# 1-Schematic_hackcard.net
KiCad netlist of a schematic drawn in EasyEDA
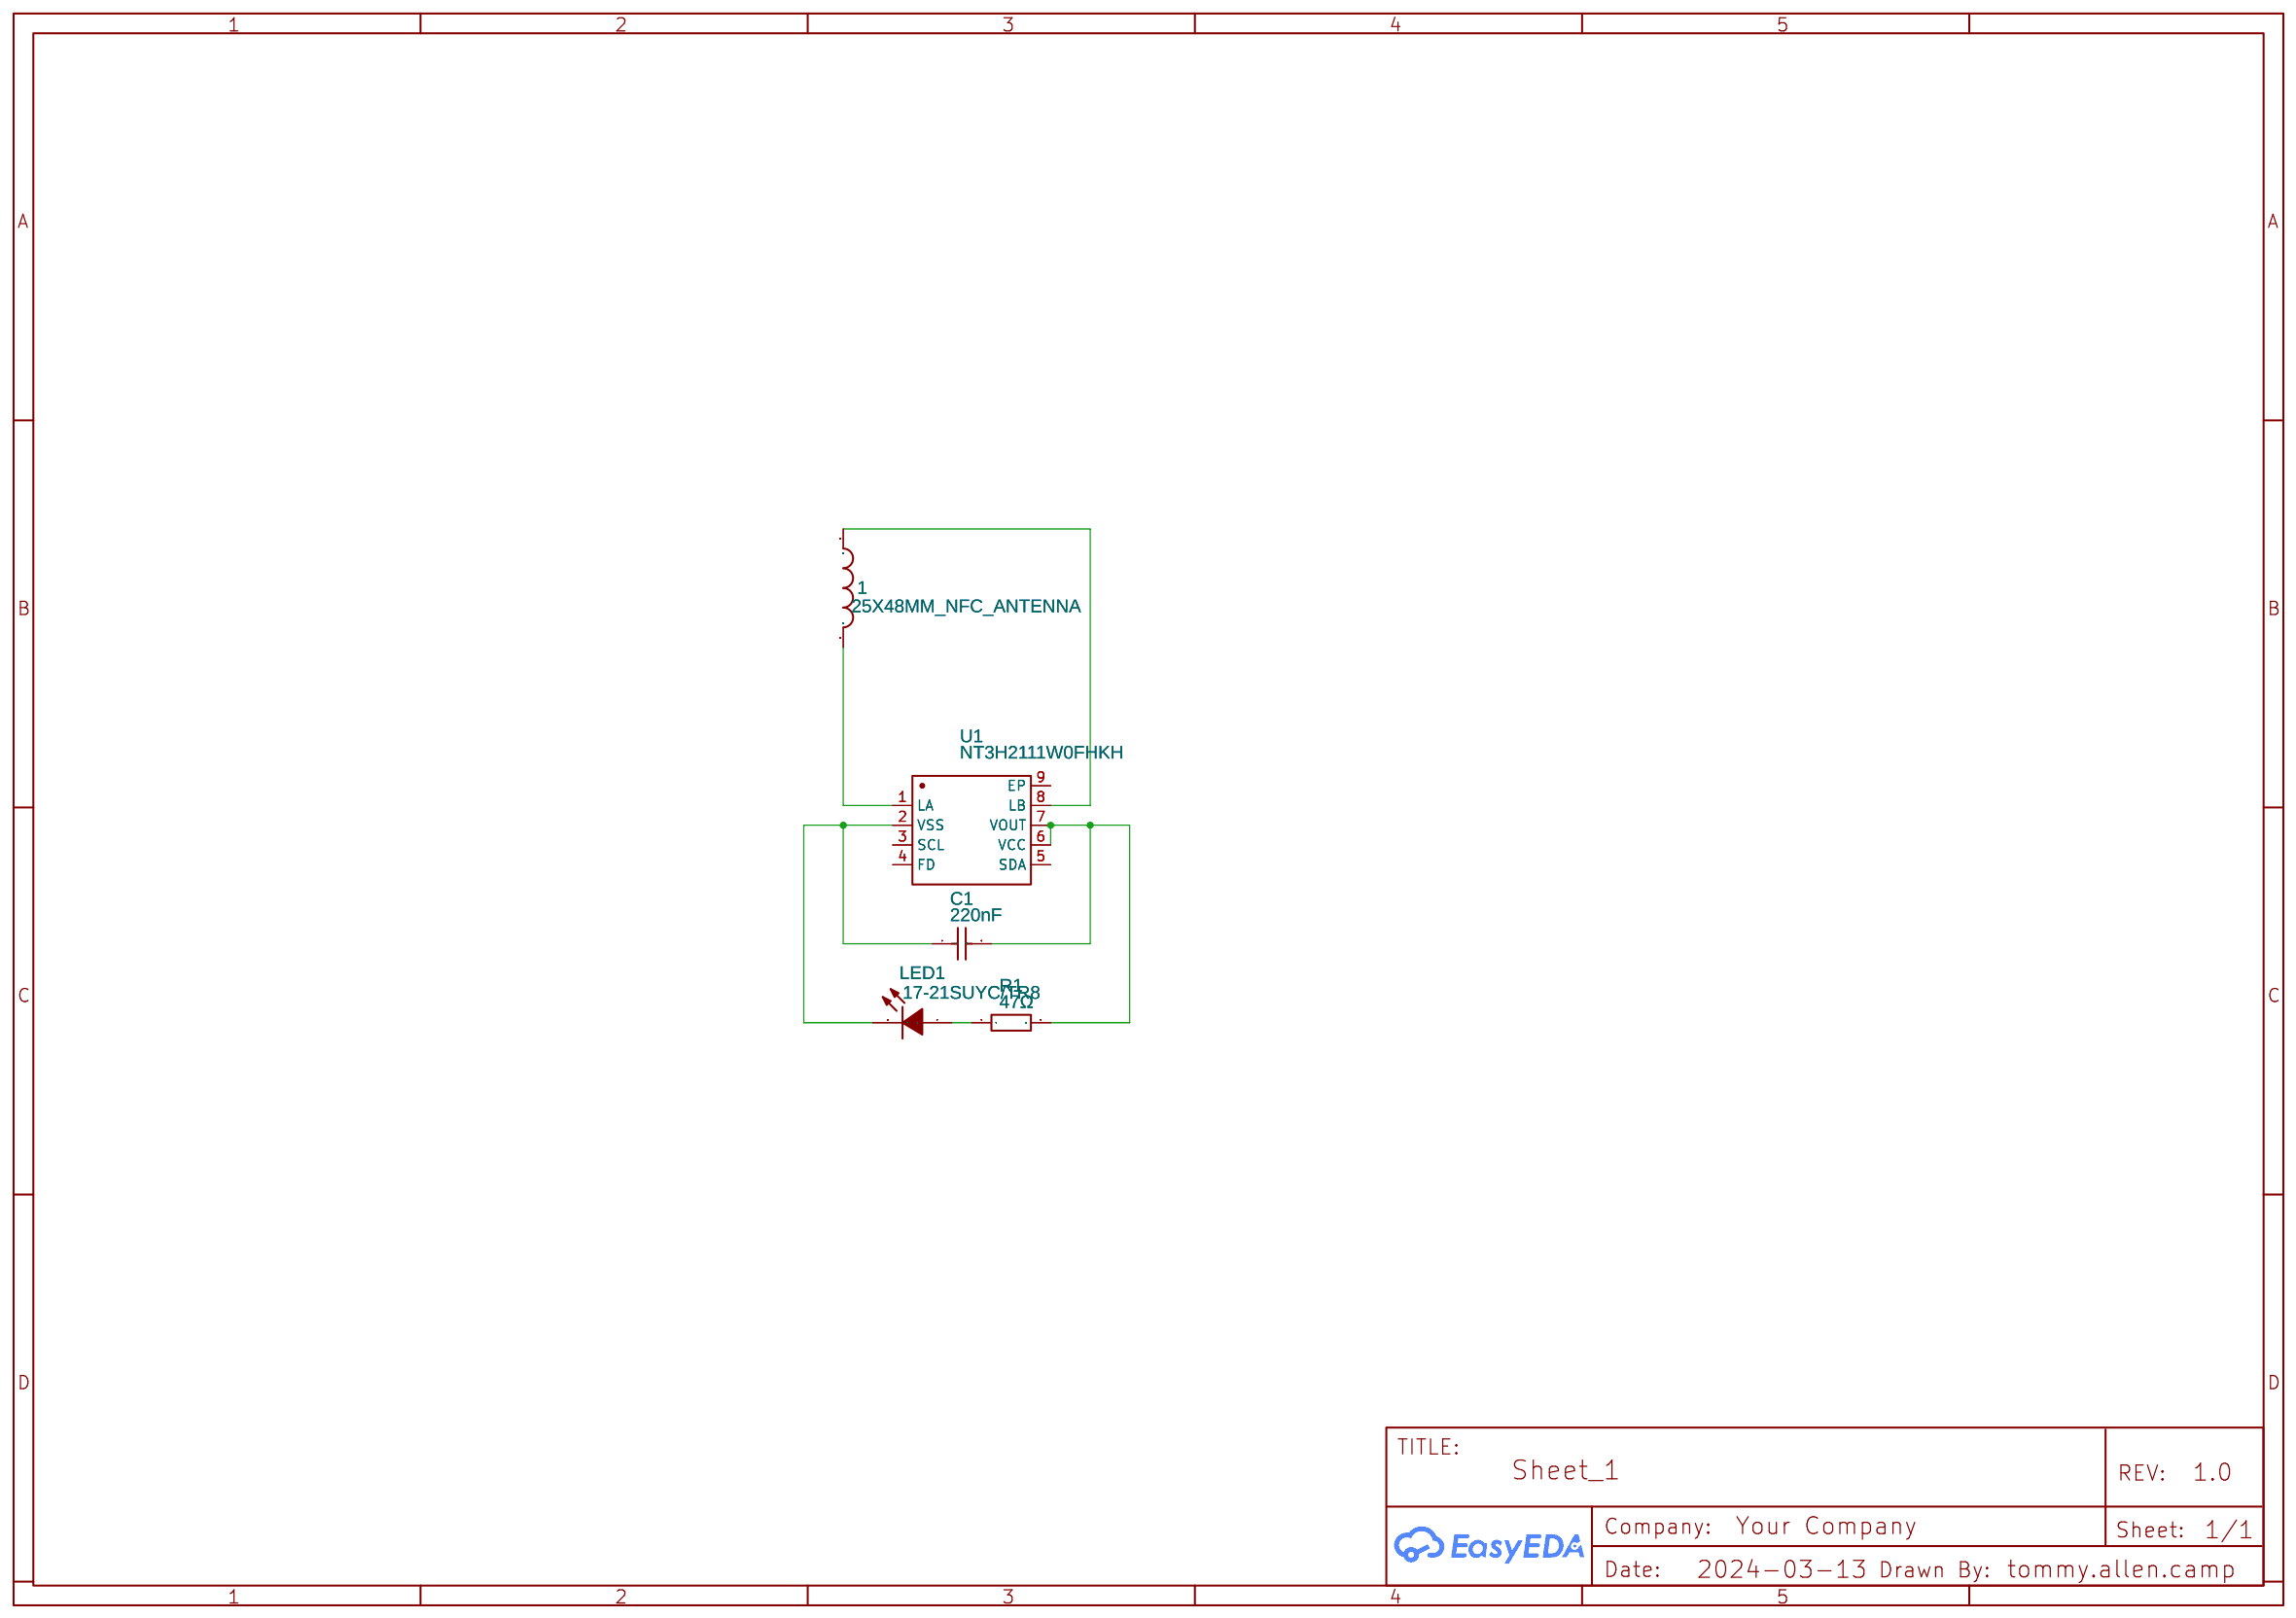
[diagram p0: schematic sheet]

(export (version "E")
  (design (tool "Eeschema 10.0.6"))
  (components
    (comp (ref "1") (value "25X48MM_NFC_ANTENNA") (libsource (lib "") (part "25X48MM_NFC_ANTENNA")))
    (comp (ref "C1")
      (value "220nF")
      (fields
        (field (name "Manufacturer Part") "CL10B224KA8NNNC")
        (field (name "Manufacturer") "SAMSUNG(三星)")
      )
      (libsource (lib "") (part "CL10B224KA8NNNC"))
    )
    (comp (ref "LED1")
      (value "17-21SUYC/TR8")
      (fields (field (name "Manufacturer Part") "KT-0805黄灯") (field (name "Manufacturer") "KENTO"))
      (libsource (lib "") (part "17-21SUYC/TR8"))
    )
    (comp (ref "R1")
      (value "47Ω")
      (fields
        (field (name "Manufacturer Part") "0603WAF470JT5E")
        (field (name "Manufacturer") "UNI-ROYAL(厚声)")
      )
      (libsource (lib "") (part "0603WAF470JT5E"))
    )
    (comp (ref "U1")
      (value "NT3H2111W0FHKH")
      (fields (field (name "Manufacturer") "NXP(恩智浦)"))
      (libsource (lib "") (part "NT3H2111W0FHKH"))
    )
  )
  (nets
    (net (code "1") (name "Net-(LED1-+)") (class "Default")
      (node (ref "LED1") (pin "1") (pinfunction "+_1") (pintype "unspecified"))
      (node (ref "R1") (pin "1") (pinfunction "1_1") (pintype "input"))
    )
    (net (code "2") (name "Net-(LED1--)") (class "Default")
      (node (ref "C1") (pin "1") (pinfunction "1_1") (pintype "input"))
      (node (ref "LED1") (pin "2") (pinfunction "-_2") (pintype "unspecified"))
      (node (ref "U1") (pin "2") (pinfunction "VSS_2") (pintype "unspecified"))
    )
    (net (code "3") (name "Net-(U1-LA)") (class "Default")
      (node (ref "1") (pin "P$2") (pinfunction "P$2_P$2") (pintype "bidirectional"))
      (node (ref "U1") (pin "1") (pinfunction "LA_1") (pintype "unspecified"))
    )
    (net (code "4") (name "Net-(U1-LB)") (class "Default")
      (node (ref "1") (pin "P$1") (pinfunction "P$1_P$1") (pintype "bidirectional"))
      (node (ref "U1") (pin "8") (pinfunction "LB_8") (pintype "unspecified"))
    )
    (net (code "5") (name "Net-(U1-VCC)") (class "Default")
      (node (ref "C1") (pin "2") (pinfunction "2_2") (pintype "input"))
      (node (ref "R1") (pin "2") (pinfunction "2_2") (pintype "input"))
      (node (ref "U1") (pin "6") (pinfunction "VCC_6") (pintype "unspecified"))
      (node (ref "U1") (pin "7") (pinfunction "VOUT_7") (pintype "unspecified"))
    )
    (net (code "6") (name "unconnected-(U1-EP-Pad9)") (class "Default")
      (node (ref "U1") (pin "9") (pinfunction "EP_9") (pintype "unspecified"))
    )
    (net (code "7") (name "unconnected-(U1-FD-Pad4)") (class "Default")
      (node (ref "U1") (pin "4") (pinfunction "FD_4") (pintype "unspecified"))
    )
    (net (code "8") (name "unconnected-(U1-SCL-Pad3)") (class "Default")
      (node (ref "U1") (pin "3") (pinfunction "SCL_3") (pintype "unspecified"))
    )
    (net (code "9") (name "unconnected-(U1-SDA-Pad5)") (class "Default")
      (node (ref "U1") (pin "5") (pinfunction "SDA_5") (pintype "unspecified"))
    )
  )
)
